# Wifi.net
KiCad netlist of a schematic drawn in Altium Designer
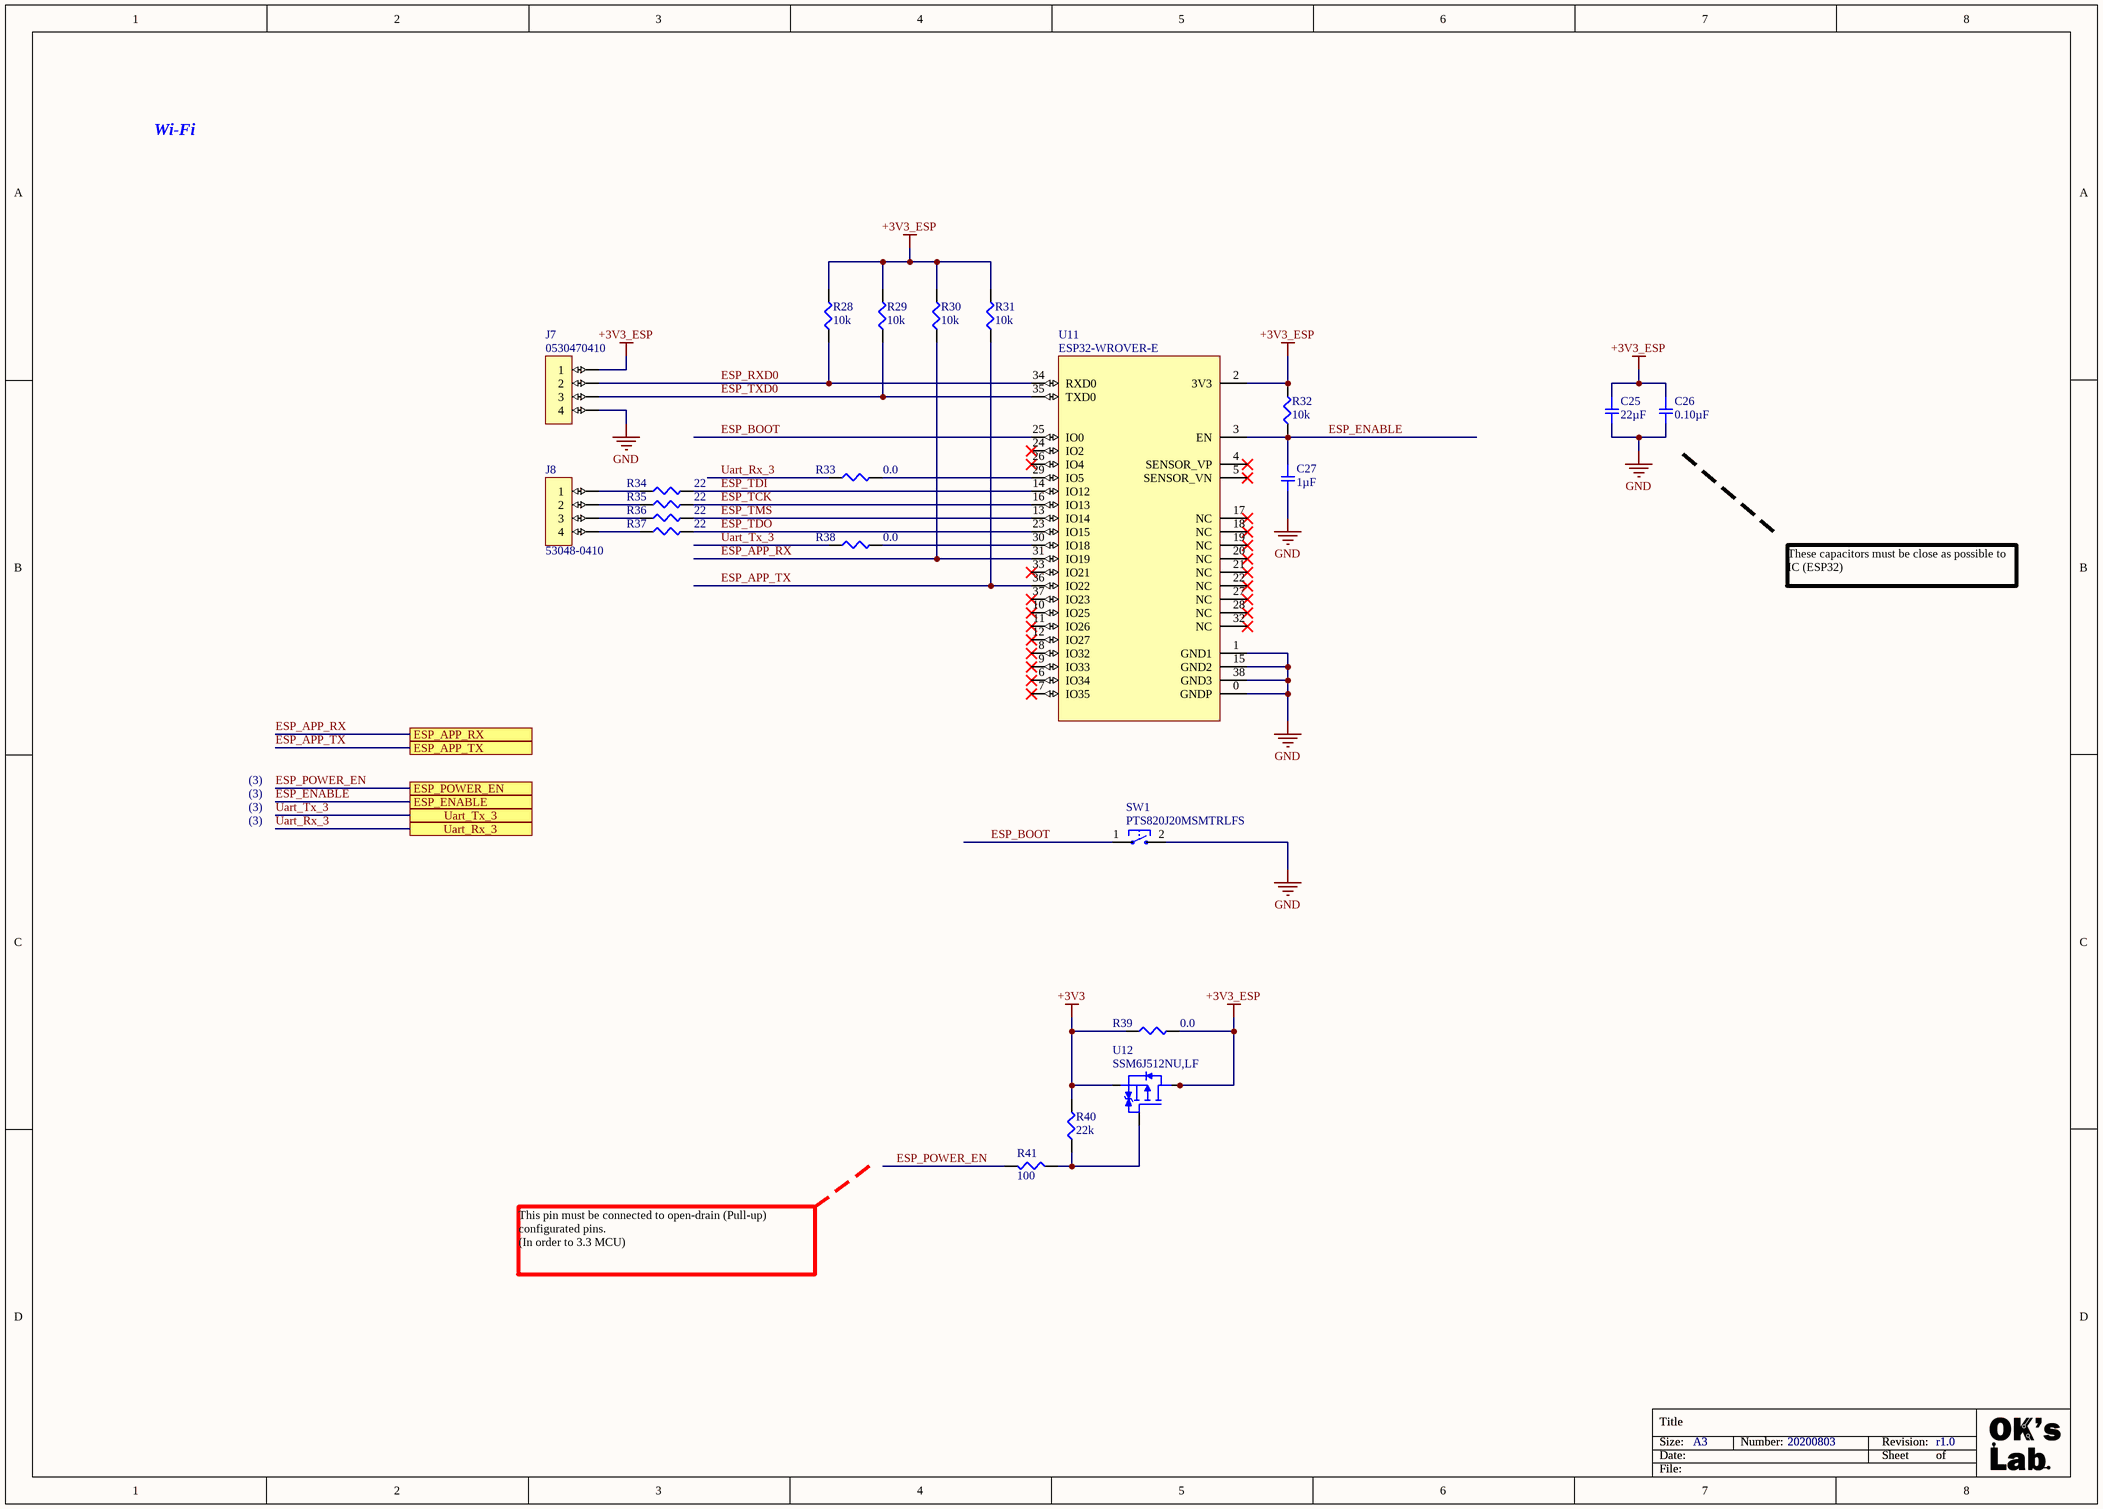
[diagram p0: Wifi.SchDoc]

(export (version "E")
  (design (tool "Eeschema 10.0.6"))
  (components
    (comp (ref "C25")
      (value "22µF")
      (footprint "SMD-0805C")
      (description "CAP CER 22UF 6.3V X6S 0805")
      (fields
        (field (name "DIGI-KEY PART NUMBER") "490-9955-1-ND")
        (field (name "PART NUMBER") "GRM21BC80J226ME51L")
      )
      (libsource (lib "capacitor_murata_0805") (part "GRM21BC80J226ME51L"))
    )
    (comp (ref "C26")
      (value "0.10µF")
      (footprint "SMD-0603C")
      (description "CAP CER 0.1UF 50V X7R 0603")
      (fields
        (field (name "DIGI-KEY PART NUMBER") "490-5798-1-ND")
        (field (name "PART NUMBER") "GCJ188R71H104KA12D")
      )
      (libsource (lib "capacitor_murata_0603") (part "GCJ188R71H104KA12D"))
    )
    (comp (ref "C27")
      (value "1µF")
      (footprint "SMD-0603C")
      (description "CAP CER 1UF 16V X7R 0603")
      (fields
        (field (name "DIGI-KEY PART NUMBER") "490-5241-1-ND")
        (field (name "PART NUMBER") "GCM188R71C105KA64D")
      )
      (libsource (lib "capacitor_murata_0603") (part "GCM188R71C105KA64D"))
    )
    (comp (ref "J7")
      (value "0530470410")
      (footprint "CONN_4_POS__053047-0410")
      (description "1.25mm (.049\") Pitch PicoBlade Wire-to-Board Header, Vertical, with Friction Lock, 4 Circuits")
      (fields (field (name "MANUFACTURER") "Molex"))
      (libsource (lib "Altium_Lib") (part "CONN_4_POS__53047-0410"))
    )
    (comp (ref "J8")
      (value "53048-0410")
      (footprint "CONN_4_POS__0530480410")
      (description "CONN HEADER R/A 4POS 1.25MM")
      (fields (field (name "MANUFACTURER") "Molex"))
      (libsource (lib "Altium_Lib") (part "CONN_4_POS__0530480410"))
    )
    (comp (ref "R28")
      (value "10k")
      (footprint "SMD-0603-RES")
      (description "RES SMD 10K OHM 1% 1/10W 0603")
      (fields
        (field (name "PART NUMBER") "ERJ-3EKF1002V")
        (field (name "DIGI-KEY PART NUMBER") "P10.0KHCT-ND")
      )
      (libsource (lib "Panasonic_ERJ_0603") (part "ERJ-3EKF1002V"))
    )
    (comp (ref "R29")
      (value "10k")
      (footprint "SMD-0603-RES")
      (description "RES SMD 10K OHM 1% 1/10W 0603")
      (fields
        (field (name "PART NUMBER") "ERJ-3EKF1002V")
        (field (name "DIGI-KEY PART NUMBER") "P10.0KHCT-ND")
      )
      (libsource (lib "Panasonic_ERJ_0603") (part "ERJ-3EKF1002V"))
    )
    (comp (ref "R30")
      (value "10k")
      (footprint "SMD-0603-RES")
      (description "RES SMD 10K OHM 1% 1/10W 0603")
      (fields
        (field (name "PART NUMBER") "ERJ-3EKF1002V")
        (field (name "DIGI-KEY PART NUMBER") "P10.0KHCT-ND")
      )
      (libsource (lib "Panasonic_ERJ_0603") (part "ERJ-3EKF1002V"))
    )
    (comp (ref "R31")
      (value "10k")
      (footprint "SMD-0603-RES")
      (description "RES SMD 10K OHM 1% 1/10W 0603")
      (fields
        (field (name "PART NUMBER") "ERJ-3EKF1002V")
        (field (name "DIGI-KEY PART NUMBER") "P10.0KHCT-ND")
      )
      (libsource (lib "Panasonic_ERJ_0603") (part "ERJ-3EKF1002V"))
    )
    (comp (ref "R32")
      (value "10k")
      (footprint "SMD-0603-RES")
      (description "RES SMD 10K OHM 1% 1/10W 0603")
      (fields
        (field (name "PART NUMBER") "ERJ-3EKF1002V")
        (field (name "DIGI-KEY PART NUMBER") "P10.0KHCT-ND")
      )
      (libsource (lib "Panasonic_ERJ_0603") (part "ERJ-3EKF1002V"))
    )
    (comp (ref "R33")
      (value "0.0")
      (footprint "SMD-0603-RES")
      (description "RES SMD 0.0OHM JUMPER 1/10W 0603")
      (fields (field (name "PART NUMBER") "ERJ-3GEY0R00V") (field (name "DIGI-KEY PART NUMBER") "P0.0GCT-ND"))
      (libsource (lib "Panasonic_ERJ_0603") (part "ERJ-3GEY0R00V"))
    )
    (comp (ref "R34")
      (value "22")
      (footprint "SMD-0603-RES")
      (description "RES SMD 22 OHM 1% 1/10W 0603")
      (fields
        (field (name "PART NUMBER") "ERJ-3EKF22R0V")
        (field (name "DIGI-KEY PART NUMBER") "P22.0HCT-ND")
      )
      (libsource (lib "Panasonic_ERJ_0603") (part "ERJ-3EKF22R0V"))
    )
    (comp (ref "R35")
      (value "22")
      (footprint "SMD-0603-RES")
      (description "RES SMD 22 OHM 1% 1/10W 0603")
      (fields
        (field (name "PART NUMBER") "ERJ-3EKF22R0V")
        (field (name "DIGI-KEY PART NUMBER") "P22.0HCT-ND")
      )
      (libsource (lib "Panasonic_ERJ_0603") (part "ERJ-3EKF22R0V"))
    )
    (comp (ref "R36")
      (value "22")
      (footprint "SMD-0603-RES")
      (description "RES SMD 22 OHM 1% 1/10W 0603")
      (fields
        (field (name "PART NUMBER") "ERJ-3EKF22R0V")
        (field (name "DIGI-KEY PART NUMBER") "P22.0HCT-ND")
      )
      (libsource (lib "Panasonic_ERJ_0603") (part "ERJ-3EKF22R0V"))
    )
    (comp (ref "R37")
      (value "22")
      (footprint "SMD-0603-RES")
      (description "RES SMD 22 OHM 1% 1/10W 0603")
      (fields
        (field (name "PART NUMBER") "ERJ-3EKF22R0V")
        (field (name "DIGI-KEY PART NUMBER") "P22.0HCT-ND")
      )
      (libsource (lib "Panasonic_ERJ_0603") (part "ERJ-3EKF22R0V"))
    )
    (comp (ref "R38")
      (value "0.0")
      (footprint "SMD-0603-RES")
      (description "RES SMD 0.0OHM JUMPER 1/10W 0603")
      (fields (field (name "PART NUMBER") "ERJ-3GEY0R00V") (field (name "DIGI-KEY PART NUMBER") "P0.0GCT-ND"))
      (libsource (lib "Panasonic_ERJ_0603") (part "ERJ-3GEY0R00V"))
    )
    (comp (ref "R39")
      (value "0.0")
      (footprint "SMD-0603-RES")
      (description "RES SMD 0.0OHM JUMPER 1/10W 0603")
      (fields (field (name "PART NUMBER") "ERJ-3GEY0R00V") (field (name "DIGI-KEY PART NUMBER") "P0.0GCT-ND"))
      (libsource (lib "Panasonic_ERJ_0603") (part "ERJ-3GEY0R00V"))
    )
    (comp (ref "R40")
      (value "22k")
      (footprint "SMD-0603-RES")
      (description "RES SMD 22K OHM 1% 1/10W 0603")
      (fields
        (field (name "DIGI-KEY PART NUMBER") "P22.0KHCT-ND")
        (field (name "MANUFACTURER") "Panasonic Electronic Components")
      )
      (libsource (lib "Panasonic_ERJ_0603") (part "ERJ-3EKF2202V"))
    )
    (comp (ref "R41")
      (value "100")
      (footprint "SMD-0603-RES")
      (description "RES SMD 100 OHM 1% 1/10W 0603")
      (fields
        (field (name "DIGI-KEY PART NUMBER") "P100HCT-ND")
        (field (name "MANUFACTURER") "Panasonic Electronic Components")
      )
      (libsource (lib "Panasonic_ERJ_0603") (part "ERJ-3EKF1000V"))
    )
    (comp (ref "SW1")
      (value "PTS820J20MSMTRLFS")
      (footprint "TACTILE_SWITCH__PTS820J25MSMTRLFS")
      (description "Switch Tactile N.O. SPST Round Button J-Bend 0.05A 12VDC 1.57N SMD T/R")
      (fields (field (name "MANUFACTURER") "ITT C&K"))
      (libsource (lib "Altium_Lib") (part "TACTILE_SWITCH__PTS820 J20M SMTR LFS"))
    )
    (comp (ref "U11")
      (value "ESP32-WROVER-E")
      (footprint "ESP32-WROVER-E")
      (description "RX TXRX MOD WIFI PCB TRACE SMD")
      (fields (field (name "MANUFACTURER") "ESPRESSIF"))
      (libsource (lib "Altium_Lib") (part "ESP32-WROVER-E (4MB)"))
    )
    (comp (ref "U12")
      (value "SSM6J512NU,LF")
      (footprint "U-DFN2020-6")
      (description "MOSFET P-CH 12V 10A 6UDFNB")
      (fields (field (name "MANUFACTURER") "Toshiba"))
      (libsource (lib "Altium_Lib") (part "MOSFET__SSM6J512NU,LF"))
    )
  )
  (nets
    (net (code "1") (name "+3V3") (class "Default")
      (node (ref "R39") (pin "1") (pinfunction "1_1") (pintype "passive"))
      (node (ref "R40") (pin "2") (pinfunction "2_2") (pintype "passive"))
      (node (ref "U12") (pin "4") (pinfunction "S_4") (pintype "passive"))
    )
    (net (code "2") (name "+3V3_ESP") (class "Default")
      (node (ref "C25") (pin "1") (pinfunction "1_1") (pintype "passive"))
      (node (ref "C26") (pin "1") (pinfunction "1_1") (pintype "passive"))
      (node (ref "J7") (pin "1") (pinfunction "1_1") (pintype "bidirectional"))
      (node (ref "R28") (pin "2") (pinfunction "2_2") (pintype "passive"))
      (node (ref "R29") (pin "2") (pinfunction "2_2") (pintype "passive"))
      (node (ref "R30") (pin "2") (pinfunction "2_2") (pintype "passive"))
      (node (ref "R31") (pin "2") (pinfunction "2_2") (pintype "passive"))
      (node (ref "R32") (pin "2") (pinfunction "2_2") (pintype "passive"))
      (node (ref "R39") (pin "2") (pinfunction "2_2") (pintype "passive"))
      (node (ref "U11") (pin "2") (pinfunction "3V3_2") (pintype "power_in"))
      (node (ref "U12") (pin "1") (pinfunction "D_1") (pintype "passive"))
      (node (ref "U12") (pin "2") (pinfunction "D_2") (pintype "passive"))
      (node (ref "U12") (pin "5") (pinfunction "D_5") (pintype "passive"))
      (node (ref "U12") (pin "6") (pinfunction "D_6") (pintype "passive"))
    )
    (net (code "3") (name "/ESP_APP_RX") (class "Default")
      (node (ref "R30") (pin "1") (pinfunction "1_1") (pintype "passive"))
      (node (ref "U11") (pin "31") (pinfunction "IO19_31") (pintype "bidirectional"))
    )
    (net (code "4") (name "/ESP_APP_TX") (class "Default")
      (node (ref "R31") (pin "1") (pinfunction "1_1") (pintype "passive"))
      (node (ref "U11") (pin "36") (pinfunction "IO22_36") (pintype "bidirectional"))
    )
    (net (code "5") (name "/ESP_BOOT") (class "Default")
      (node (ref "SW1") (pin "1") (pinfunction "1_1") (pintype "passive"))
      (node (ref "U11") (pin "25") (pinfunction "IO0_25") (pintype "bidirectional"))
    )
    (net (code "6") (name "/ESP_ENABLE") (class "Default")
      (node (ref "C27") (pin "1") (pinfunction "1_1") (pintype "passive"))
      (node (ref "R32") (pin "1") (pinfunction "1_1") (pintype "passive"))
      (node (ref "U11") (pin "3") (pinfunction "EN_3") (pintype "power_in"))
    )
    (net (code "7") (name "/ESP_POWER_EN") (class "Default")
      (node (ref "R41") (pin "2") (pinfunction "2_2") (pintype "passive"))
    )
    (net (code "8") (name "/ESP_RXD0") (class "Default")
      (node (ref "J7") (pin "2") (pinfunction "2_2") (pintype "bidirectional"))
      (node (ref "R28") (pin "1") (pinfunction "1_1") (pintype "passive"))
      (node (ref "U11") (pin "34") (pinfunction "RXD0_34") (pintype "bidirectional"))
    )
    (net (code "9") (name "/ESP_TCK") (class "Default")
      (node (ref "R35") (pin "2") (pinfunction "2_2") (pintype "passive"))
      (node (ref "U11") (pin "16") (pinfunction "IO13_16") (pintype "bidirectional"))
    )
    (net (code "10") (name "/ESP_TDI") (class "Default")
      (node (ref "R34") (pin "2") (pinfunction "2_2") (pintype "passive"))
      (node (ref "U11") (pin "14") (pinfunction "IO12_14") (pintype "bidirectional"))
    )
    (net (code "11") (name "/ESP_TDO") (class "Default")
      (node (ref "R37") (pin "2") (pinfunction "2_2") (pintype "passive"))
      (node (ref "U11") (pin "23") (pinfunction "IO15_23") (pintype "bidirectional"))
    )
    (net (code "12") (name "/ESP_TMS") (class "Default")
      (node (ref "R36") (pin "2") (pinfunction "2_2") (pintype "passive"))
      (node (ref "U11") (pin "13") (pinfunction "IO14_13") (pintype "bidirectional"))
    )
    (net (code "13") (name "/ESP_TXD0") (class "Default")
      (node (ref "J7") (pin "3") (pinfunction "3_3") (pintype "bidirectional"))
      (node (ref "R29") (pin "1") (pinfunction "1_1") (pintype "passive"))
      (node (ref "U11") (pin "35") (pinfunction "TXD0_35") (pintype "bidirectional"))
    )
    (net (code "14") (name "/Uart_Rx_3") (class "Default")
      (node (ref "R33") (pin "1") (pinfunction "1_1") (pintype "passive"))
    )
    (net (code "15") (name "/Uart_Tx_3") (class "Default")
      (node (ref "R38") (pin "1") (pinfunction "1_1") (pintype "passive"))
    )
    (net (code "16") (name "GND") (class "Default")
      (node (ref "C25") (pin "2") (pinfunction "2_2") (pintype "passive"))
      (node (ref "C26") (pin "2") (pinfunction "2_2") (pintype "passive"))
      (node (ref "C27") (pin "2") (pinfunction "2_2") (pintype "passive"))
      (node (ref "J7") (pin "4") (pinfunction "4_4") (pintype "bidirectional"))
      (node (ref "SW1") (pin "2") (pinfunction "2_2") (pintype "passive"))
      (node (ref "U11") (pin "0") (pinfunction "GNDP_0") (pintype "power_in"))
      (node (ref "U11") (pin "1") (pinfunction "GND1_1") (pintype "power_in"))
      (node (ref "U11") (pin "15") (pinfunction "GND2_15") (pintype "power_in"))
      (node (ref "U11") (pin "38") (pinfunction "GND3_38") (pintype "power_in"))
    )
    (net (code "17") (name "Net-(J8-Pad1)") (class "Default")
      (node (ref "J8") (pin "1") (pinfunction "1_1") (pintype "bidirectional"))
      (node (ref "R34") (pin "1") (pinfunction "1_1") (pintype "passive"))
    )
    (net (code "18") (name "Net-(J8-Pad2)") (class "Default")
      (node (ref "J8") (pin "2") (pinfunction "2_2") (pintype "bidirectional"))
      (node (ref "R35") (pin "1") (pinfunction "1_1") (pintype "passive"))
    )
    (net (code "19") (name "Net-(J8-Pad3)") (class "Default")
      (node (ref "J8") (pin "3") (pinfunction "3_3") (pintype "bidirectional"))
      (node (ref "R36") (pin "1") (pinfunction "1_1") (pintype "passive"))
    )
    (net (code "20") (name "Net-(J8-Pad4)") (class "Default")
      (node (ref "J8") (pin "4") (pinfunction "4_4") (pintype "bidirectional"))
      (node (ref "R37") (pin "1") (pinfunction "1_1") (pintype "passive"))
    )
    (net (code "21") (name "Net-(U11-IO5)") (class "Default")
      (node (ref "R33") (pin "2") (pinfunction "2_2") (pintype "passive"))
      (node (ref "U11") (pin "29") (pinfunction "IO5_29") (pintype "bidirectional"))
    )
    (net (code "22") (name "Net-(U11-IO18)") (class "Default")
      (node (ref "R38") (pin "2") (pinfunction "2_2") (pintype "passive"))
      (node (ref "U11") (pin "30") (pinfunction "IO18_30") (pintype "bidirectional"))
    )
    (net (code "23") (name "Net-(U12-G)") (class "Default")
      (node (ref "R40") (pin "1") (pinfunction "1_1") (pintype "passive"))
      (node (ref "R41") (pin "1") (pinfunction "1_1") (pintype "passive"))
      (node (ref "U12") (pin "3") (pinfunction "G_3") (pintype "passive"))
    )
    (net (code "24") (name "unconnected-(U11-IO2-Pad24)") (class "Default")
      (node (ref "U11") (pin "24") (pinfunction "IO2_24") (pintype "bidirectional+no_connect"))
    )
    (net (code "25") (name "unconnected-(U11-IO4-Pad26)") (class "Default")
      (node (ref "U11") (pin "26") (pinfunction "IO4_26") (pintype "bidirectional+no_connect"))
    )
    (net (code "26") (name "unconnected-(U11-IO21-Pad33)") (class "Default")
      (node (ref "U11") (pin "33") (pinfunction "IO21_33") (pintype "bidirectional+no_connect"))
    )
    (net (code "27") (name "unconnected-(U11-IO23-Pad37)") (class "Default")
      (node (ref "U11") (pin "37") (pinfunction "IO23_37") (pintype "bidirectional+no_connect"))
    )
    (net (code "28") (name "unconnected-(U11-IO25-Pad10)") (class "Default")
      (node (ref "U11") (pin "10") (pinfunction "IO25_10") (pintype "bidirectional+no_connect"))
    )
    (net (code "29") (name "unconnected-(U11-IO26-Pad11)") (class "Default")
      (node (ref "U11") (pin "11") (pinfunction "IO26_11") (pintype "bidirectional+no_connect"))
    )
    (net (code "30") (name "unconnected-(U11-IO27-Pad12)") (class "Default")
      (node (ref "U11") (pin "12") (pinfunction "IO27_12") (pintype "bidirectional+no_connect"))
    )
    (net (code "31") (name "unconnected-(U11-IO32-Pad8)") (class "Default")
      (node (ref "U11") (pin "8") (pinfunction "IO32_8") (pintype "bidirectional+no_connect"))
    )
    (net (code "32") (name "unconnected-(U11-IO33-Pad9)") (class "Default")
      (node (ref "U11") (pin "9") (pinfunction "IO33_9") (pintype "bidirectional+no_connect"))
    )
    (net (code "33") (name "unconnected-(U11-IO34-Pad6)") (class "Default")
      (node (ref "U11") (pin "6") (pinfunction "IO34_6") (pintype "bidirectional+no_connect"))
    )
    (net (code "34") (name "unconnected-(U11-IO35-Pad7)") (class "Default")
      (node (ref "U11") (pin "7") (pinfunction "IO35_7") (pintype "bidirectional+no_connect"))
    )
    (net (code "35") (name "unconnected-(U11-NC-Pad17)") (class "Default")
      (node (ref "U11") (pin "17") (pinfunction "NC_17") (pintype "passive+no_connect"))
    )
    (net (code "36") (name "unconnected-(U11-NC-Pad18)") (class "Default")
      (node (ref "U11") (pin "18") (pinfunction "NC_18") (pintype "passive+no_connect"))
    )
    (net (code "37") (name "unconnected-(U11-NC-Pad19)") (class "Default")
      (node (ref "U11") (pin "19") (pinfunction "NC_19") (pintype "passive+no_connect"))
    )
    (net (code "38") (name "unconnected-(U11-NC-Pad20)") (class "Default")
      (node (ref "U11") (pin "20") (pinfunction "NC_20") (pintype "passive+no_connect"))
    )
    (net (code "39") (name "unconnected-(U11-NC-Pad21)") (class "Default")
      (node (ref "U11") (pin "21") (pinfunction "NC_21") (pintype "passive+no_connect"))
    )
    (net (code "40") (name "unconnected-(U11-NC-Pad22)") (class "Default")
      (node (ref "U11") (pin "22") (pinfunction "NC_22") (pintype "passive+no_connect"))
    )
    (net (code "41") (name "unconnected-(U11-NC-Pad27)") (class "Default")
      (node (ref "U11") (pin "27") (pinfunction "NC_27") (pintype "passive+no_connect"))
    )
    (net (code "42") (name "unconnected-(U11-NC-Pad28)") (class "Default")
      (node (ref "U11") (pin "28") (pinfunction "NC_28") (pintype "passive+no_connect"))
    )
    (net (code "43") (name "unconnected-(U11-NC-Pad32)") (class "Default")
      (node (ref "U11") (pin "32") (pinfunction "NC_32") (pintype "passive+no_connect"))
    )
    (net (code "44") (name "unconnected-(U11-SENSOR_VN-Pad5)") (class "Default")
      (node (ref "U11") (pin "5") (pinfunction "SENSOR_VN_5") (pintype "power_in+no_connect"))
    )
    (net (code "45") (name "unconnected-(U11-SENSOR_VP-Pad4)") (class "Default")
      (node (ref "U11") (pin "4") (pinfunction "SENSOR_VP_4") (pintype "power_in+no_connect"))
    )
  )
)
